# Pulse_to_DTMF_Converter.net
KiCad netlist of a schematic drawn in Altium Designer
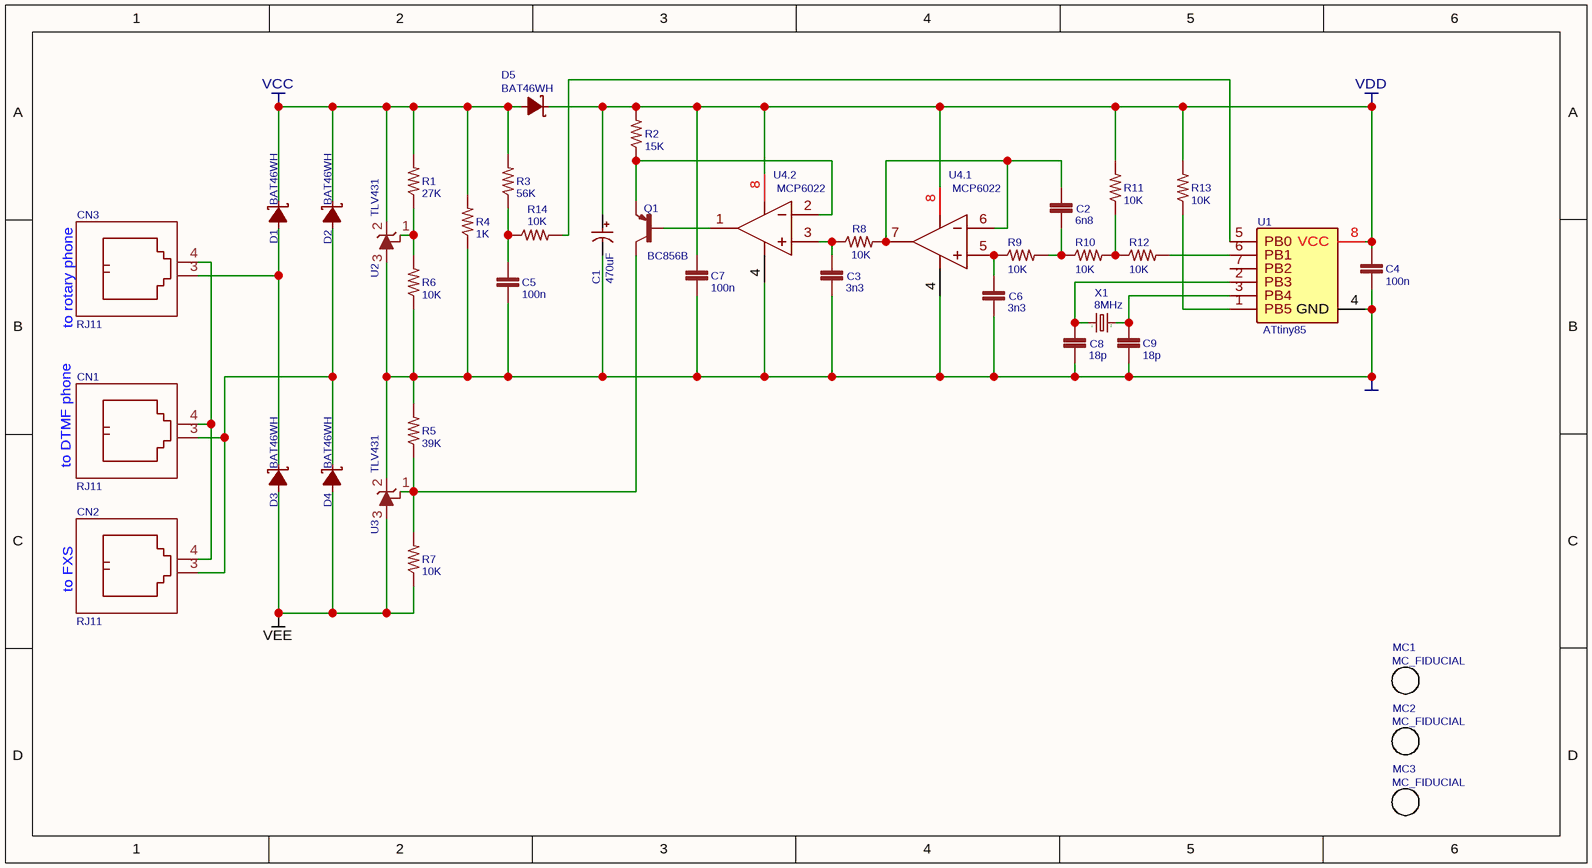
[diagram p0: Pulse_to_DTMF_Converter.schdoc]

(export (version "E")
  (design (tool "Eeschema 10.0.6"))
  (components
    (comp (ref "C1")
      (value "470uF")
      (fields (field (name "BOM_MANUFACTURER PART") "?"))
      (libsource (lib "altium-import") (part "root_3__"))
    )
    (comp (ref "C2")
      (value "6n8")
      (description "6n8 1206 50V")
      (fields (field (name "BOM_MANUFACTURER PART") "?"))
      (libsource (lib "") (part "root_0___1"))
    )
    (comp (ref "C3")
      (value "3n3")
      (description "3n3 1206 50V")
      (fields (field (name "BOM_MANUFACTURER PART") "?"))
      (libsource (lib "") (part "root_0___1"))
    )
    (comp (ref "C4")
      (value "100n")
      (description "100n 1206 50V")
      (fields (field (name "BOM_MANUFACTURER PART") "?"))
      (libsource (lib "") (part "root_0___1"))
    )
    (comp (ref "C5")
      (value "100n")
      (description "100n 1206 50V")
      (fields (field (name "BOM_MANUFACTURER PART") "?"))
      (libsource (lib "") (part "root_0___1"))
    )
    (comp (ref "C6")
      (value "3n3")
      (description "3n3 1206 50V")
      (fields (field (name "BOM_MANUFACTURER PART") "?"))
      (libsource (lib "") (part "root_0___1"))
    )
    (comp (ref "C7")
      (value "100n")
      (description "100n 1206 50V")
      (fields (field (name "BOM_MANUFACTURER PART") "?"))
      (libsource (lib "") (part "root_0___1"))
    )
    (comp (ref "C8")
      (value "18p")
      (description "18p 1206 50V")
      (fields (field (name "BOM_MANUFACTURER PART") "?"))
      (libsource (lib "") (part "root_0___1"))
    )
    (comp (ref "C9")
      (value "18p")
      (description "18p 1206 50V")
      (fields (field (name "BOM_MANUFACTURER PART") "?"))
      (libsource (lib "") (part "root_0___1"))
    )
    (comp (ref "CN1")
      (value "RJ11")
      (fields (field (name "BOM_MANUFACTURER PART") "?"))
      (libsource (lib "altium-import") (part "root_1__"))
    )
    (comp (ref "CN2")
      (value "RJ11")
      (fields (field (name "BOM_MANUFACTURER PART") "?"))
      (libsource (lib "altium-import") (part "root_1__"))
    )
    (comp (ref "CN3")
      (value "RJ11")
      (fields (field (name "BOM_MANUFACTURER PART") "?"))
      (libsource (lib "altium-import") (part "root_1__"))
    )
    (comp (ref "D1")
      (value "BAT46WH")
      (fields (field (name "BOM_MANUFACTURER PART") "?"))
      (libsource (lib "") (part "root_3___1"))
    )
    (comp (ref "D2")
      (value "BAT46WH")
      (fields (field (name "BOM_MANUFACTURER PART") "?"))
      (libsource (lib "") (part "root_3___1"))
    )
    (comp (ref "D3")
      (value "BAT46WH")
      (fields (field (name "BOM_MANUFACTURER PART") "?"))
      (libsource (lib "") (part "root_3___1"))
    )
    (comp (ref "D4")
      (value "BAT46WH")
      (fields (field (name "BOM_MANUFACTURER PART") "?"))
      (libsource (lib "") (part "root_3___1"))
    )
    (comp (ref "D5")
      (value "BAT46WH")
      (fields (field (name "BOM_MANUFACTURER PART") "?"))
      (libsource (lib "altium-import") (part "root_2__"))
    )
    (comp (ref "MC1")
      (value "MC_FIDUCIAL")
      (fields (field (name "CONTRIBUTOR") "LieBtrau"))
      (libsource (lib "altium-import") (part "root_0__"))
    )
    (comp (ref "MC2")
      (value "MC_FIDUCIAL")
      (fields (field (name "CONTRIBUTOR") "LieBtrau"))
      (libsource (lib "altium-import") (part "root_0__"))
    )
    (comp (ref "MC3")
      (value "MC_FIDUCIAL")
      (fields (field (name "CONTRIBUTOR") "LieBtrau"))
      (libsource (lib "altium-import") (part "root_0__"))
    )
    (comp (ref "Q1")
      (value "BC856B")
      (fields (field (name "BOM_MANUFACTURER PART") "?"))
      (libsource (lib "") (part "root_0___2"))
    )
    (comp (ref "R1")
      (value "27K")
      (description "Yageo RC1206")
      (fields (field (name "BOM_MANUFACTURER PART") "?"))
      (libsource (lib "") (part "root_1___1"))
    )
    (comp (ref "R2")
      (value "15K")
      (description "Yageo RC1206")
      (fields (field (name "BOM_MANUFACTURER PART") "?"))
      (libsource (lib "") (part "root_1___1"))
    )
    (comp (ref "R3")
      (value "56K")
      (description "Yageo RC1206")
      (fields (field (name "BOM_MANUFACTURER PART") "?"))
      (libsource (lib "") (part "root_1___1"))
    )
    (comp (ref "R4")
      (value "1K")
      (fields (field (name "BOM_MANUFACTURER PART") "?"))
      (libsource (lib "") (part "root_1___1"))
    )
    (comp (ref "R5")
      (value "39K")
      (description "Yageo RC1206")
      (fields (field (name "BOM_MANUFACTURER PART") "?"))
      (libsource (lib "") (part "root_1___1"))
    )
    (comp (ref "R6")
      (value "10K")
      (description "Yageo RC1206")
      (fields (field (name "BOM_MANUFACTURER PART") "?"))
      (libsource (lib "") (part "root_1___1"))
    )
    (comp (ref "R7")
      (value "10K")
      (description "Yageo RC1206")
      (fields (field (name "BOM_MANUFACTURER PART") "?"))
      (libsource (lib "") (part "root_1___1"))
    )
    (comp (ref "R8")
      (value "10K")
      (description "Yageo RC1206")
      (fields (field (name "BOM_MANUFACTURER PART") "?"))
      (libsource (lib "") (part "root_0___4"))
    )
    (comp (ref "R9")
      (value "10K")
      (description "Yageo RC1206")
      (fields (field (name "BOM_MANUFACTURER PART") "?"))
      (libsource (lib "") (part "root_0___4"))
    )
    (comp (ref "R10")
      (value "10K")
      (description "Yageo RC1206")
      (fields (field (name "BOM_MANUFACTURER PART") "?"))
      (libsource (lib "") (part "root_0___4"))
    )
    (comp (ref "R11")
      (value "10K")
      (description "Yageo RC1206")
      (fields (field (name "BOM_MANUFACTURER PART") "?"))
      (libsource (lib "") (part "root_1___1"))
    )
    (comp (ref "R12")
      (value "10K")
      (description "Yageo RC1206")
      (fields (field (name "BOM_MANUFACTURER PART") "?"))
      (libsource (lib "") (part "root_0___4"))
    )
    (comp (ref "R13")
      (value "10K")
      (description "Yageo RC1206")
      (fields (field (name "BOM_MANUFACTURER PART") "?"))
      (libsource (lib "") (part "root_1___1"))
    )
    (comp (ref "R14")
      (value "10K")
      (description "Yageo RC1206")
      (fields (field (name "BOM_MANUFACTURER PART") "?"))
      (libsource (lib "") (part "root_0___4"))
    )
    (comp (ref "U1")
      (value "ATtiny85")
      (fields (field (name "BOM_MANUFACTURER PART") "?"))
      (libsource (lib "") (part "root_0___5"))
    )
    (comp (ref "U2")
      (value "TLV431")
      (fields (field (name "BOM_MANUFACTURER PART") "?"))
      (libsource (lib "") (part "root_0___7"))
    )
    (comp (ref "U3")
      (value "TLV431")
      (fields (field (name "BOM_MANUFACTURER PART") "?"))
      (libsource (lib "") (part "root_0___7"))
    )
    (comp (ref "U4.1")
      (value "MCP6022")
      (fields (field (name "BOM_MANUFACTURER PART") "?"))
      (libsource (lib "") (part "root_0___3"))
    )
    (comp (ref "U4.2")
      (value "MCP6022")
      (fields (field (name "BOM_MANUFACTURER PART") "?"))
      (libsource (lib "") (part "root_0___8"))
    )
    (comp (ref "X1")
      (value "8MHz")
      (description "8MHz, 18pF")
      (fields (field (name "BOM_MANUFACTURER PART") "?"))
      (libsource (lib "") (part "root_0___6"))
    )
  )
  (nets
    (net (code "1") (name "GND") (class "Default")
      (node (ref "C1") (pin "2") (pinfunction "2_2") (pintype "passive"))
      (node (ref "C3") (pin "2") (pinfunction "2_2") (pintype "passive"))
      (node (ref "C4") (pin "2") (pinfunction "2_2") (pintype "passive"))
      (node (ref "C5") (pin "2") (pinfunction "2_2") (pintype "passive"))
      (node (ref "C6") (pin "2") (pinfunction "2_2") (pintype "passive"))
      (node (ref "C7") (pin "2") (pinfunction "2_2") (pintype "passive"))
      (node (ref "C8") (pin "2") (pinfunction "2_2") (pintype "passive"))
      (node (ref "C9") (pin "2") (pinfunction "2_2") (pintype "passive"))
      (node (ref "R4") (pin "1") (pinfunction "1_1") (pintype "passive"))
      (node (ref "R5") (pin "2") (pinfunction "2_2") (pintype "passive"))
      (node (ref "R6") (pin "1") (pinfunction "1_1") (pintype "passive"))
      (node (ref "U1") (pin "4") (pinfunction "GND_4") (pintype "passive"))
      (node (ref "U2") (pin "3") (pinfunction "A_3") (pintype "passive"))
      (node (ref "U3") (pin "2") (pinfunction "C_2") (pintype "passive"))
      (node (ref "U4.1") (pin "4") (pinfunction "VSS_4") (pintype "passive"))
      (node (ref "U4.2") (pin "4") (pinfunction "VSS_4") (pintype "passive"))
    )
    (net (code "2") (name "Net-(C2-Pad2)") (class "Default")
      (node (ref "C2") (pin "2") (pinfunction "2_2") (pintype "passive"))
      (node (ref "R10") (pin "1") (pinfunction "1_1") (pintype "passive"))
      (node (ref "R9") (pin "2") (pinfunction "2_2") (pintype "passive"))
    )
    (net (code "3") (name "Net-(C5-Pad1)") (class "Default")
      (node (ref "C5") (pin "1") (pinfunction "1_1") (pintype "passive"))
      (node (ref "R14") (pin "1") (pinfunction "1_1") (pintype "passive"))
      (node (ref "R3") (pin "1") (pinfunction "1_1") (pintype "passive"))
    )
    (net (code "4") (name "Net-(CN1-Pad4)") (class "Default")
      (node (ref "CN1") (pin "4") (pinfunction "4_4") (pintype "passive"))
      (node (ref "CN2") (pin "4") (pinfunction "4_4") (pintype "passive"))
      (node (ref "CN3") (pin "4") (pinfunction "4_4") (pintype "passive"))
    )
    (net (code "5") (name "Net-(D3-K)") (class "Default")
      (node (ref "CN3") (pin "3") (pinfunction "3_3") (pintype "passive"))
      (node (ref "D1") (pin "A") (pinfunction "A_A") (pintype "passive"))
      (node (ref "D3") (pin "C") (pinfunction "K_C") (pintype "passive"))
    )
    (net (code "6") (name "Net-(D4-K)") (class "Default")
      (node (ref "CN1") (pin "3") (pinfunction "3_3") (pintype "passive"))
      (node (ref "CN2") (pin "3") (pinfunction "3_3") (pintype "passive"))
      (node (ref "D2") (pin "A") (pinfunction "A_A") (pintype "passive"))
      (node (ref "D4") (pin "C") (pinfunction "K_C") (pintype "passive"))
    )
    (net (code "7") (name "Net-(Q1-B)") (class "Default")
      (node (ref "Q1") (pin "1") (pinfunction "B_1") (pintype "passive"))
      (node (ref "U4.2") (pin "1") (pinfunction "VOUTA_1") (pintype "passive"))
    )
    (net (code "8") (name "Net-(Q1-C)") (class "Default")
      (node (ref "Q1") (pin "3") (pinfunction "C_3") (pintype "passive"))
      (node (ref "R5") (pin "1") (pinfunction "1_1") (pintype "passive"))
      (node (ref "R7") (pin "2") (pinfunction "2_2") (pintype "passive"))
      (node (ref "U3") (pin "1") (pinfunction "R_1") (pintype "passive"))
    )
    (net (code "9") (name "Net-(Q1-E)") (class "Default")
      (node (ref "Q1") (pin "2") (pinfunction "E_2") (pintype "passive"))
      (node (ref "R2") (pin "1") (pinfunction "1_1") (pintype "passive"))
      (node (ref "U4.2") (pin "2") (pinfunction "VINA-_2") (pintype "passive"))
    )
    (net (code "10") (name "Net-(R10-Pad2)") (class "Default")
      (node (ref "R10") (pin "2") (pinfunction "2_2") (pintype "passive"))
      (node (ref "R11") (pin "1") (pinfunction "1_1") (pintype "passive"))
      (node (ref "R12") (pin "1") (pinfunction "1_1") (pintype "passive"))
    )
    (net (code "11") (name "Net-(U1-PB0)") (class "Default")
      (node (ref "R14") (pin "2") (pinfunction "2_2") (pintype "passive"))
      (node (ref "U1") (pin "5") (pinfunction "PB0_5") (pintype "passive"))
    )
    (net (code "12") (name "Net-(U1-PB1)") (class "Default")
      (node (ref "R12") (pin "2") (pinfunction "2_2") (pintype "passive"))
      (node (ref "U1") (pin "6") (pinfunction "PB1_6") (pintype "passive"))
    )
    (net (code "13") (name "Net-(U1-PB3)") (class "Default")
      (node (ref "C8") (pin "1") (pinfunction "1_1") (pintype "passive"))
      (node (ref "U1") (pin "2") (pinfunction "PB3_2") (pintype "passive"))
      (node (ref "X1") (pin "1") (pinfunction "1_1") (pintype "passive"))
    )
    (net (code "14") (name "Net-(U1-PB4)") (class "Default")
      (node (ref "C9") (pin "1") (pinfunction "1_1") (pintype "passive"))
      (node (ref "U1") (pin "3") (pinfunction "PB4_3") (pintype "passive"))
      (node (ref "X1") (pin "2") (pinfunction "2_2") (pintype "passive"))
    )
    (net (code "15") (name "Net-(U1-PB5)") (class "Default")
      (node (ref "R13") (pin "1") (pinfunction "1_1") (pintype "passive"))
      (node (ref "U1") (pin "1") (pinfunction "PB5_1") (pintype "passive"))
    )
    (net (code "16") (name "Net-(U2-R)") (class "Default")
      (node (ref "R1") (pin "1") (pinfunction "1_1") (pintype "passive"))
      (node (ref "R6") (pin "2") (pinfunction "2_2") (pintype "passive"))
      (node (ref "U2") (pin "1") (pinfunction "R_1") (pintype "passive"))
    )
    (net (code "17") (name "Net-(U4.1-VINB+)") (class "Default")
      (node (ref "C6") (pin "1") (pinfunction "1_1") (pintype "passive"))
      (node (ref "R9") (pin "1") (pinfunction "1_1") (pintype "passive"))
      (node (ref "U4.1") (pin "5") (pinfunction "VINB+_5") (pintype "passive"))
    )
    (net (code "18") (name "Net-(U4.1-VINB-)") (class "Default")
      (node (ref "C2") (pin "1") (pinfunction "1_1") (pintype "passive"))
      (node (ref "R8") (pin "2") (pinfunction "2_2") (pintype "passive"))
      (node (ref "U4.1") (pin "6") (pinfunction "VINB-_6") (pintype "passive"))
      (node (ref "U4.1") (pin "7") (pinfunction "VOUTB_7") (pintype "passive"))
    )
    (net (code "19") (name "Net-(U4.2-VINA+)") (class "Default")
      (node (ref "C3") (pin "1") (pinfunction "1_1") (pintype "passive"))
      (node (ref "R8") (pin "1") (pinfunction "1_1") (pintype "passive"))
      (node (ref "U4.2") (pin "3") (pinfunction "VINA+_3") (pintype "passive"))
    )
    (net (code "20") (name "VCC") (class "Default")
      (node (ref "D1") (pin "C") (pinfunction "K_C") (pintype "passive"))
      (node (ref "D2") (pin "C") (pinfunction "K_C") (pintype "passive"))
      (node (ref "D5") (pin "A") (pinfunction "A_A") (pintype "passive"))
      (node (ref "R1") (pin "2") (pinfunction "2_2") (pintype "passive"))
      (node (ref "R3") (pin "2") (pinfunction "2_2") (pintype "passive"))
      (node (ref "R4") (pin "2") (pinfunction "2_2") (pintype "passive"))
      (node (ref "U2") (pin "2") (pinfunction "C_2") (pintype "passive"))
    )
    (net (code "21") (name "VDD") (class "Default")
      (node (ref "C1") (pin "1") (pinfunction "1_1") (pintype "passive"))
      (node (ref "C4") (pin "1") (pinfunction "1_1") (pintype "passive"))
      (node (ref "C7") (pin "1") (pinfunction "1_1") (pintype "passive"))
      (node (ref "D5") (pin "C") (pinfunction "K_C") (pintype "passive"))
      (node (ref "R11") (pin "2") (pinfunction "2_2") (pintype "passive"))
      (node (ref "R13") (pin "2") (pinfunction "2_2") (pintype "passive"))
      (node (ref "R2") (pin "2") (pinfunction "2_2") (pintype "passive"))
      (node (ref "U1") (pin "8") (pinfunction "VCC_8") (pintype "passive"))
      (node (ref "U4.1") (pin "8") (pinfunction "VDD_8") (pintype "passive"))
      (node (ref "U4.2") (pin "8") (pinfunction "VDD_8") (pintype "passive"))
    )
    (net (code "22") (name "VEE") (class "Default")
      (node (ref "D3") (pin "A") (pinfunction "A_A") (pintype "passive"))
      (node (ref "D4") (pin "A") (pinfunction "A_A") (pintype "passive"))
      (node (ref "R7") (pin "1") (pinfunction "1_1") (pintype "passive"))
      (node (ref "U3") (pin "3") (pinfunction "A_3") (pintype "passive"))
    )
    (net (code "23") (name "unconnected-(U1-PB2-Pad7)") (class "Default")
      (node (ref "U1") (pin "7") (pinfunction "PB2_7") (pintype "passive"))
    )
  )
)
